# Main_ASCII.net
KiCad netlist of a schematic drawn in Altium Designer
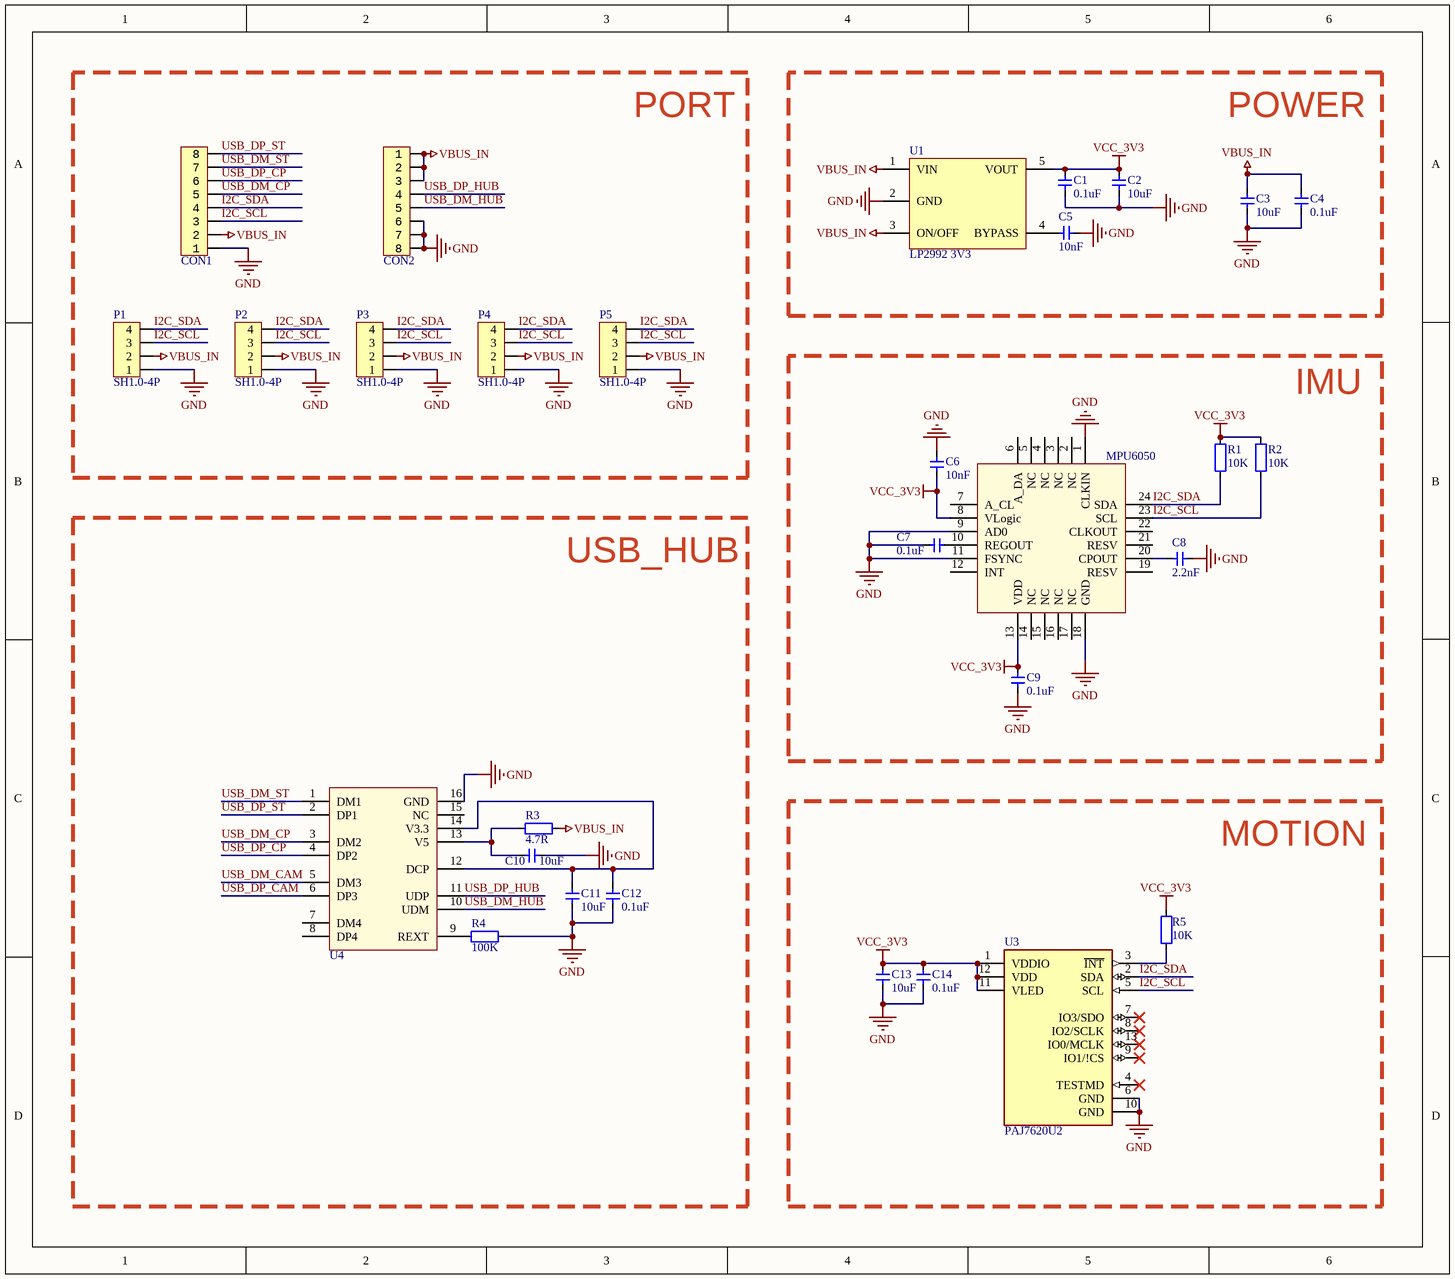
[diagram p0: Main_ASCII.SchDoc]

(export (version "E")
  (design (tool "Eeschema 10.0.6"))
  (components
    (comp (ref "C1")
      (value "0.1uF")
      (footprint "CAP_0402")
      (description "Capacitor")
      (libsource (lib "MyPcbLib") (part "电容-0402"))
    )
    (comp (ref "C2")
      (value "10uF")
      (footprint "CAP_0402")
      (description "Capacitor")
      (libsource (lib "MyPcbLib") (part "电容-0402"))
    )
    (comp (ref "C3")
      (value "10uF")
      (footprint "CAP_0402")
      (description "Capacitor")
      (libsource (lib "MyPcbLib") (part "电容-0402"))
    )
    (comp (ref "C4")
      (value "0.1uF")
      (footprint "CAP_0402")
      (description "Capacitor")
      (libsource (lib "MyPcbLib") (part "电容-0402"))
    )
    (comp (ref "C5")
      (value "10nF")
      (footprint "CAP_0402")
      (description "Capacitor")
      (libsource (lib "MyPcbLib") (part "电容-0402"))
    )
    (comp (ref "C6")
      (value "10nF")
      (footprint "CAP_0402")
      (description "Capacitor")
      (libsource (lib "MyPcbLib") (part "电容-0402"))
    )
    (comp (ref "C7")
      (value "0.1uF")
      (footprint "CAP_0402")
      (description "Capacitor")
      (libsource (lib "MyPcbLib") (part "电容-0402"))
    )
    (comp (ref "C8")
      (value "2.2nF")
      (footprint "CAP_0402")
      (description "Capacitor")
      (libsource (lib "MyPcbLib") (part "电容-0402"))
    )
    (comp (ref "C9")
      (value "0.1uF")
      (footprint "CAP_0402")
      (description "Capacitor")
      (libsource (lib "MyPcbLib") (part "电容-0402"))
    )
    (comp (ref "C10")
      (value "10uF")
      (footprint "CAP_0402")
      (description "Capacitor")
      (libsource (lib "MyPcbLib") (part "电容-0402"))
    )
    (comp (ref "C11")
      (value "10uF")
      (footprint "CAP_0402")
      (description "Capacitor")
      (libsource (lib "MyPcbLib") (part "电容-0402"))
    )
    (comp (ref "C12")
      (value "0.1uF")
      (footprint "CAP_0402")
      (description "Capacitor")
      (libsource (lib "MyPcbLib") (part "电容-0402"))
    )
    (comp (ref "C13")
      (value "10uF")
      (footprint "CAP_0402")
      (description "Capacitor")
      (libsource (lib "MyPcbLib") (part "电容-0402"))
    )
    (comp (ref "C14")
      (value "0.1uF")
      (footprint "CAP_0402")
      (description "Capacitor")
      (libsource (lib "MyPcbLib") (part "电容-0402"))
    )
    (comp (ref "CON1")
      (value "FFC_0.5_8")
      (footprint "FFC_0.5_8")
      (description "FFC")
      (libsource (lib "") (part "FFC_0.5_8_1"))
    )
    (comp (ref "CON2")
      (value "FFC_0.5_8")
      (footprint "FFC_0.5_8")
      (description "FFC")
      (libsource (lib "KitSprout") (part "FFC_0.5_8"))
    )
    (comp (ref "P1") (value "SH1.0-4P") (footprint "SH1.0-4P") (libsource (lib "MyPcbLib") (part "SH1.0-4P")))
    (comp (ref "P2") (value "SH1.0-4P") (footprint "SH1.0-4P") (libsource (lib "MyPcbLib") (part "SH1.0-4P")))
    (comp (ref "P3") (value "SH1.0-4P") (footprint "SH1.0-4P") (libsource (lib "MyPcbLib") (part "SH1.0-4P")))
    (comp (ref "P4") (value "SH1.0-4P") (footprint "SH1.0-4P") (libsource (lib "MyPcbLib") (part "SH1.0-4P")))
    (comp (ref "P5") (value "SH1.0-4P") (footprint "SH1.0-4P") (libsource (lib "MyPcbLib") (part "SH1.0-4P")))
    (comp (ref "R1")
      (value "10K")
      (footprint "RES_0402")
      (description "Resistor")
      (libsource (lib "MyPcbLib") (part "电阻-0402"))
    )
    (comp (ref "R2")
      (value "10K")
      (footprint "RES_0402")
      (description "Resistor")
      (libsource (lib "MyPcbLib") (part "电阻-0402"))
    )
    (comp (ref "R3")
      (value "4.7R")
      (footprint "RES_0402")
      (description "Resistor")
      (libsource (lib "") (part "电阻-0402_1"))
    )
    (comp (ref "R4")
      (value "100K")
      (footprint "RES_0402")
      (description "Resistor")
      (libsource (lib "") (part "电阻-0402_1"))
    )
    (comp (ref "R5")
      (value "10K")
      (footprint "RES_0402")
      (description "Resistor")
      (libsource (lib "") (part "电阻-0402_2"))
    )
    (comp (ref "U1")
      (value "LP2992 3V3")
      (footprint "SOT23-5")
      (description "LDO")
      (libsource (lib "MyPcbLib") (part "LP2992"))
    )
    (comp (ref "U2")
      (value "MPU6050")
      (footprint "QFN-24")
      (description "六轴传感器")
      (libsource (lib "mLib") (part "MPU6050"))
    )
    (comp (ref "U3")
      (value "PAJ7620U2")
      (footprint "PAJ7620U2")
      (description "module sensorPAJ7620U2 : 54/TRAY, 5400/BOX, 32400/CARTON")
      (fields (field (name "MF") "Pixart"))
      (libsource (lib "MyPcbLib") (part "PAJ7620U2"))
    )
    (comp (ref "U4")
      (value "HS8836A")
      (footprint "SO-16N")
      (description "USB2.0 HUB")
      (libsource (lib "MyPcbLib") (part "HS8836A"))
    )
  )
  (nets
    (net (code "1") (name "/I2C_SCL") (class "Default")
      (node (ref "CON1") (pin "3") (pinfunction "3_3") (pintype "passive"))
      (node (ref "P1") (pin "3") (pinfunction "3_3") (pintype "passive"))
      (node (ref "P2") (pin "3") (pinfunction "3_3") (pintype "passive"))
      (node (ref "P3") (pin "3") (pinfunction "3_3") (pintype "passive"))
      (node (ref "P4") (pin "3") (pinfunction "3_3") (pintype "passive"))
      (node (ref "P5") (pin "3") (pinfunction "3_3") (pintype "passive"))
      (node (ref "R2") (pin "1") (pinfunction "1_1") (pintype "passive"))
      (node (ref "U2") (pin "23") (pinfunction "SCL_23") (pintype "passive"))
      (node (ref "U3") (pin "5") (pinfunction "SCL_5") (pintype "input"))
    )
    (net (code "2") (name "/I2C_SDA") (class "Default")
      (node (ref "CON1") (pin "4") (pinfunction "4_4") (pintype "passive"))
      (node (ref "P1") (pin "4") (pinfunction "4_4") (pintype "passive"))
      (node (ref "P2") (pin "4") (pinfunction "4_4") (pintype "passive"))
      (node (ref "P3") (pin "4") (pinfunction "4_4") (pintype "passive"))
      (node (ref "P4") (pin "4") (pinfunction "4_4") (pintype "passive"))
      (node (ref "P5") (pin "4") (pinfunction "4_4") (pintype "passive"))
      (node (ref "R1") (pin "1") (pinfunction "1_1") (pintype "passive"))
      (node (ref "U2") (pin "24") (pinfunction "SDA_24") (pintype "passive"))
      (node (ref "U3") (pin "2") (pinfunction "SDA_2") (pintype "bidirectional"))
    )
    (net (code "3") (name "/USB_DM_CAM") (class "Default")
      (node (ref "U4") (pin "5") (pinfunction "DM3_5") (pintype "passive"))
    )
    (net (code "4") (name "/USB_DM_CP") (class "Default")
      (node (ref "CON1") (pin "5") (pinfunction "5_5") (pintype "passive"))
      (node (ref "U4") (pin "3") (pinfunction "DM2_3") (pintype "passive"))
    )
    (net (code "5") (name "/USB_DM_HUB") (class "Default")
      (node (ref "CON2") (pin "5") (pinfunction "5_5") (pintype "passive"))
      (node (ref "U4") (pin "10") (pinfunction "UDM_10") (pintype "passive"))
    )
    (net (code "6") (name "/USB_DM_ST") (class "Default")
      (node (ref "CON1") (pin "7") (pinfunction "7_7") (pintype "passive"))
      (node (ref "U4") (pin "1") (pinfunction "DM1_1") (pintype "passive"))
    )
    (net (code "7") (name "/USB_DP_CAM") (class "Default")
      (node (ref "U4") (pin "6") (pinfunction "DP3_6") (pintype "passive"))
    )
    (net (code "8") (name "/USB_DP_CP") (class "Default")
      (node (ref "CON1") (pin "6") (pinfunction "6_6") (pintype "passive"))
      (node (ref "U4") (pin "4") (pinfunction "DP2_4") (pintype "passive"))
    )
    (net (code "9") (name "/USB_DP_HUB") (class "Default")
      (node (ref "CON2") (pin "4") (pinfunction "4_4") (pintype "passive"))
      (node (ref "U4") (pin "11") (pinfunction "UDP_11") (pintype "passive"))
    )
    (net (code "10") (name "/USB_DP_ST") (class "Default")
      (node (ref "CON1") (pin "8") (pinfunction "8_8") (pintype "passive"))
      (node (ref "U4") (pin "2") (pinfunction "DP1_2") (pintype "passive"))
    )
    (net (code "11") (name "GND") (class "Default")
      (node (ref "C1") (pin "1") (pinfunction "1_1") (pintype "passive"))
      (node (ref "C10") (pin "1") (pinfunction "1_1") (pintype "passive"))
      (node (ref "C11") (pin "2") (pinfunction "2_2") (pintype "passive"))
      (node (ref "C12") (pin "2") (pinfunction "2_2") (pintype "passive"))
      (node (ref "C13") (pin "2") (pinfunction "2_2") (pintype "passive"))
      (node (ref "C14") (pin "2") (pinfunction "2_2") (pintype "passive"))
      (node (ref "C2") (pin "1") (pinfunction "1_1") (pintype "passive"))
      (node (ref "C3") (pin "1") (pinfunction "1_1") (pintype "passive"))
      (node (ref "C4") (pin "1") (pinfunction "1_1") (pintype "passive"))
      (node (ref "C5") (pin "1") (pinfunction "1_1") (pintype "passive"))
      (node (ref "C6") (pin "2") (pinfunction "2_2") (pintype "passive"))
      (node (ref "C7") (pin "2") (pinfunction "2_2") (pintype "passive"))
      (node (ref "C8") (pin "1") (pinfunction "1_1") (pintype "passive"))
      (node (ref "C9") (pin "1") (pinfunction "1_1") (pintype "passive"))
      (node (ref "CON1") (pin "1") (pinfunction "1_1") (pintype "passive"))
      (node (ref "CON2") (pin "6") (pinfunction "6_6") (pintype "passive"))
      (node (ref "CON2") (pin "7") (pinfunction "7_7") (pintype "passive"))
      (node (ref "CON2") (pin "8") (pinfunction "8_8") (pintype "passive"))
      (node (ref "P1") (pin "1") (pinfunction "1_1") (pintype "passive"))
      (node (ref "P2") (pin "1") (pinfunction "1_1") (pintype "passive"))
      (node (ref "P3") (pin "1") (pinfunction "1_1") (pintype "passive"))
      (node (ref "P4") (pin "1") (pinfunction "1_1") (pintype "passive"))
      (node (ref "P5") (pin "1") (pinfunction "1_1") (pintype "passive"))
      (node (ref "R4") (pin "1") (pinfunction "1_1") (pintype "passive"))
      (node (ref "U1") (pin "2") (pinfunction "GND_2") (pintype "passive"))
      (node (ref "U2") (pin "1") (pinfunction "CLKIN_1") (pintype "passive"))
      (node (ref "U2") (pin "11") (pinfunction "FSYNC_11") (pintype "passive"))
      (node (ref "U2") (pin "18") (pinfunction "GND_18") (pintype "passive"))
      (node (ref "U2") (pin "9") (pinfunction "AD0_9") (pintype "passive"))
      (node (ref "U3") (pin "10") (pinfunction "GND_10") (pintype "passive"))
      (node (ref "U3") (pin "6") (pinfunction "GND_6") (pintype "passive"))
      (node (ref "U4") (pin "16") (pinfunction "GND_16") (pintype "passive"))
    )
    (net (code "12") (name "Net-(U1-BYPASS)") (class "Default")
      (node (ref "C5") (pin "2") (pinfunction "2_2") (pintype "passive"))
      (node (ref "U1") (pin "4") (pinfunction "BYPASS_4") (pintype "passive"))
    )
    (net (code "13") (name "Net-(U2-CPOUT)") (class "Default")
      (node (ref "C8") (pin "2") (pinfunction "2_2") (pintype "passive"))
      (node (ref "U2") (pin "20") (pinfunction "CPOUT_20") (pintype "passive"))
    )
    (net (code "14") (name "Net-(U2-REGOUT)") (class "Default")
      (node (ref "C7") (pin "1") (pinfunction "1_1") (pintype "passive"))
      (node (ref "U2") (pin "10") (pinfunction "REGOUT_10") (pintype "passive"))
    )
    (net (code "15") (name "Net-(U3-~{INT})") (class "Default")
      (node (ref "R5") (pin "2") (pinfunction "2_2") (pintype "passive"))
      (node (ref "U3") (pin "3") (pinfunction "~{INT}_3") (pintype "output"))
    )
    (net (code "16") (name "Net-(U4-DCP)") (class "Default")
      (node (ref "C11") (pin "1") (pinfunction "1_1") (pintype "passive"))
      (node (ref "C12") (pin "1") (pinfunction "1_1") (pintype "passive"))
      (node (ref "U4") (pin "12") (pinfunction "DCP_12") (pintype "passive"))
      (node (ref "U4") (pin "14") (pinfunction "V3.3_14") (pintype "passive"))
    )
    (net (code "17") (name "Net-(U4-REXT)") (class "Default")
      (node (ref "R4") (pin "2") (pinfunction "2_2") (pintype "passive"))
      (node (ref "U4") (pin "9") (pinfunction "REXT_9") (pintype "passive"))
    )
    (net (code "18") (name "Net-(U4-V5)") (class "Default")
      (node (ref "C10") (pin "2") (pinfunction "2_2") (pintype "passive"))
      (node (ref "R3") (pin "2") (pinfunction "2_2") (pintype "passive"))
      (node (ref "U4") (pin "13") (pinfunction "V5_13") (pintype "passive"))
    )
    (net (code "19") (name "VBUS_IN") (class "Default")
      (node (ref "C3") (pin "2") (pinfunction "2_2") (pintype "passive"))
      (node (ref "C4") (pin "2") (pinfunction "2_2") (pintype "passive"))
      (node (ref "CON1") (pin "2") (pinfunction "2_2") (pintype "passive"))
      (node (ref "CON2") (pin "1") (pinfunction "1_1") (pintype "passive"))
      (node (ref "CON2") (pin "2") (pinfunction "2_2") (pintype "passive"))
      (node (ref "CON2") (pin "3") (pinfunction "3_3") (pintype "passive"))
      (node (ref "P1") (pin "2") (pinfunction "2_2") (pintype "passive"))
      (node (ref "P2") (pin "2") (pinfunction "2_2") (pintype "passive"))
      (node (ref "P3") (pin "2") (pinfunction "2_2") (pintype "passive"))
      (node (ref "P4") (pin "2") (pinfunction "2_2") (pintype "passive"))
      (node (ref "P5") (pin "2") (pinfunction "2_2") (pintype "passive"))
      (node (ref "R3") (pin "1") (pinfunction "1_1") (pintype "passive"))
      (node (ref "U1") (pin "1") (pinfunction "VIN_1") (pintype "passive"))
      (node (ref "U1") (pin "3") (pinfunction "ON/OFF_3") (pintype "passive"))
    )
    (net (code "20") (name "VCC_3V3") (class "Default")
      (node (ref "C1") (pin "2") (pinfunction "2_2") (pintype "passive"))
      (node (ref "C13") (pin "1") (pinfunction "1_1") (pintype "passive"))
      (node (ref "C14") (pin "1") (pinfunction "1_1") (pintype "passive"))
      (node (ref "C2") (pin "2") (pinfunction "2_2") (pintype "passive"))
      (node (ref "C6") (pin "1") (pinfunction "1_1") (pintype "passive"))
      (node (ref "C9") (pin "2") (pinfunction "2_2") (pintype "passive"))
      (node (ref "R1") (pin "2") (pinfunction "2_2") (pintype "passive"))
      (node (ref "R2") (pin "2") (pinfunction "2_2") (pintype "passive"))
      (node (ref "R5") (pin "1") (pinfunction "1_1") (pintype "passive"))
      (node (ref "U1") (pin "5") (pinfunction "VOUT_5") (pintype "passive"))
      (node (ref "U2") (pin "13") (pinfunction "VDD_13") (pintype "passive"))
      (node (ref "U2") (pin "8") (pinfunction "VLogic_8") (pintype "passive"))
      (node (ref "U3") (pin "1") (pinfunction "VDDIO_1") (pintype "power_in"))
      (node (ref "U3") (pin "11") (pinfunction "VLED_11") (pintype "power_in"))
      (node (ref "U3") (pin "12") (pinfunction "VDD_12") (pintype "power_in"))
    )
    (net (code "21") (name "unconnected-(U2-A_CL-Pad7)") (class "Default")
      (node (ref "U2") (pin "7") (pinfunction "A_CL_7") (pintype "passive"))
    )
    (net (code "22") (name "unconnected-(U2-A_DA-Pad6)") (class "Default")
      (node (ref "U2") (pin "6") (pinfunction "A_DA_6") (pintype "passive"))
    )
    (net (code "23") (name "unconnected-(U2-CLKOUT-Pad22)") (class "Default")
      (node (ref "U2") (pin "22") (pinfunction "CLKOUT_22") (pintype "passive"))
    )
    (net (code "24") (name "unconnected-(U2-INT-Pad12)") (class "Default")
      (node (ref "U2") (pin "12") (pinfunction "INT_12") (pintype "passive"))
    )
    (net (code "25") (name "unconnected-(U2-NC-Pad2)") (class "Default")
      (node (ref "U2") (pin "2") (pinfunction "NC_2") (pintype "passive"))
    )
    (net (code "26") (name "unconnected-(U2-NC-Pad3)") (class "Default")
      (node (ref "U2") (pin "3") (pinfunction "NC_3") (pintype "passive"))
    )
    (net (code "27") (name "unconnected-(U2-NC-Pad4)") (class "Default")
      (node (ref "U2") (pin "4") (pinfunction "NC_4") (pintype "passive"))
    )
    (net (code "28") (name "unconnected-(U2-NC-Pad5)") (class "Default")
      (node (ref "U2") (pin "5") (pinfunction "NC_5") (pintype "passive"))
    )
    (net (code "29") (name "unconnected-(U2-NC-Pad14)") (class "Default")
      (node (ref "U2") (pin "14") (pinfunction "NC_14") (pintype "passive"))
    )
    (net (code "30") (name "unconnected-(U2-NC-Pad15)") (class "Default")
      (node (ref "U2") (pin "15") (pinfunction "NC_15") (pintype "passive"))
    )
    (net (code "31") (name "unconnected-(U2-NC-Pad16)") (class "Default")
      (node (ref "U2") (pin "16") (pinfunction "NC_16") (pintype "passive"))
    )
    (net (code "32") (name "unconnected-(U2-NC-Pad17)") (class "Default")
      (node (ref "U2") (pin "17") (pinfunction "NC_17") (pintype "passive"))
    )
    (net (code "33") (name "unconnected-(U2-RESV-Pad19)") (class "Default")
      (node (ref "U2") (pin "19") (pinfunction "RESV_19") (pintype "passive"))
    )
    (net (code "34") (name "unconnected-(U2-RESV-Pad21)") (class "Default")
      (node (ref "U2") (pin "21") (pinfunction "RESV_21") (pintype "passive"))
    )
    (net (code "35") (name "unconnected-(U3-IO0{slash}MCLK-Pad13)") (class "Default")
      (node (ref "U3") (pin "13") (pinfunction "IO0/MCLK_13") (pintype "bidirectional+no_connect"))
    )
    (net (code "36") (name "unconnected-(U3-IO1{slash}!CS-Pad9)") (class "Default")
      (node (ref "U3") (pin "9") (pinfunction "IO1/!CS_9") (pintype "bidirectional+no_connect"))
    )
    (net (code "37") (name "unconnected-(U3-IO2{slash}SCLK-Pad8)") (class "Default")
      (node (ref "U3") (pin "8") (pinfunction "IO2/SCLK_8") (pintype "bidirectional+no_connect"))
    )
    (net (code "38") (name "unconnected-(U3-IO3{slash}SDO-Pad7)") (class "Default")
      (node (ref "U3") (pin "7") (pinfunction "IO3/SDO_7") (pintype "bidirectional+no_connect"))
    )
    (net (code "39") (name "unconnected-(U3-TESTMD-Pad4)") (class "Default")
      (node (ref "U3") (pin "4") (pinfunction "TESTMD_4") (pintype "input+no_connect"))
    )
    (net (code "40") (name "unconnected-(U4-DM4-Pad7)") (class "Default")
      (node (ref "U4") (pin "7") (pinfunction "DM4_7") (pintype "passive"))
    )
    (net (code "41") (name "unconnected-(U4-DP4-Pad8)") (class "Default")
      (node (ref "U4") (pin "8") (pinfunction "DP4_8") (pintype "passive"))
    )
    (net (code "42") (name "unconnected-(U4-NC-Pad15)") (class "Default")
      (node (ref "U4") (pin "15") (pinfunction "NC_15") (pintype "passive"))
    )
  )
)
